# Water_Level_Indicator.net
KiCad netlist of a schematic drawn in Altium Designer
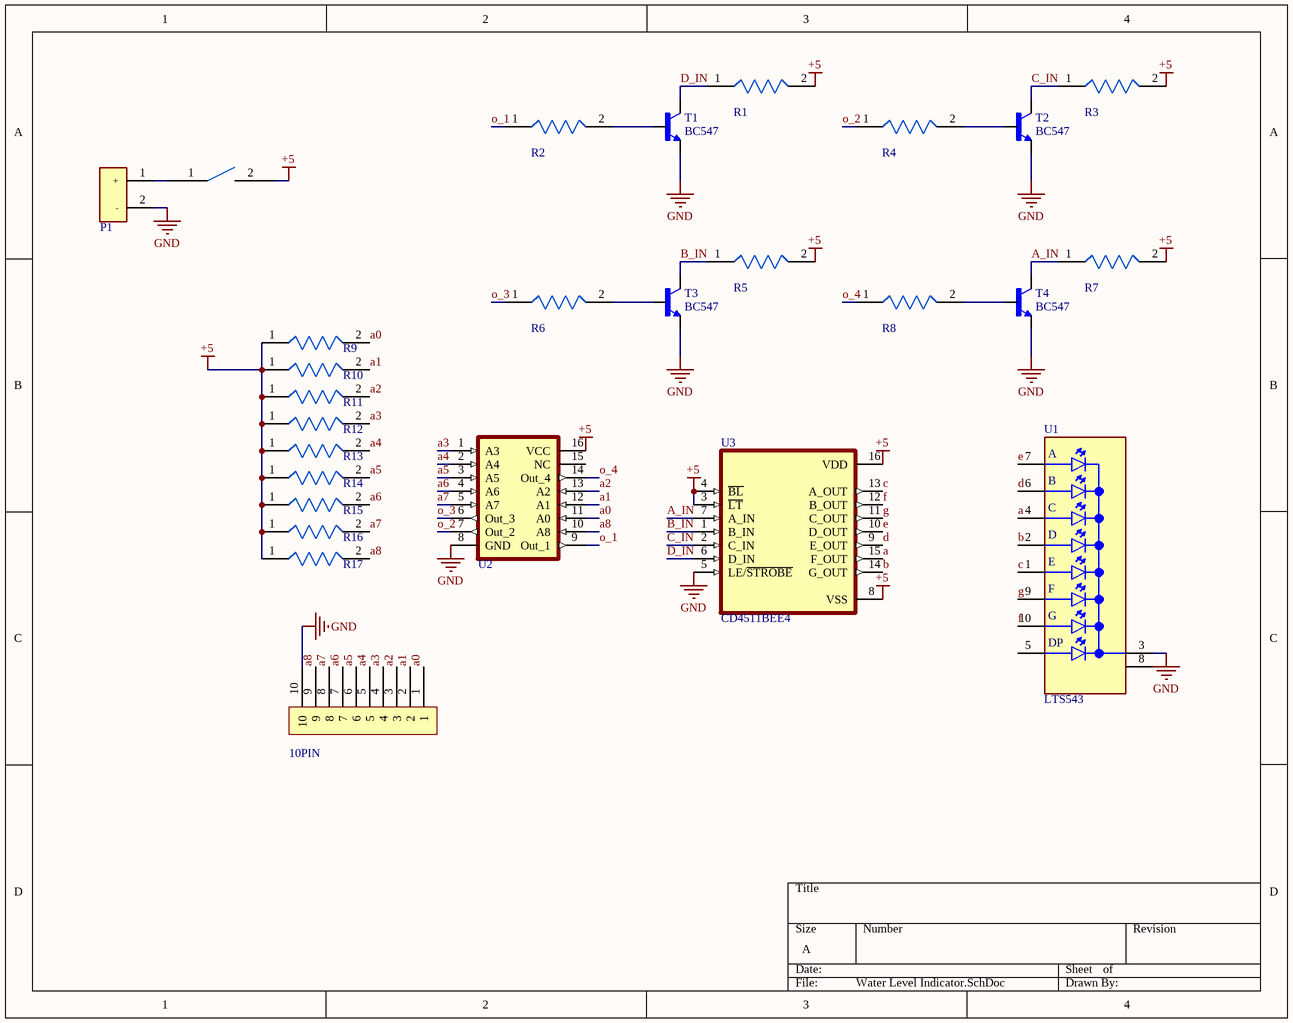
[diagram p0: Water Level Indicator.SchDoc]

(export (version "E")
  (design (tool "Eeschema 10.0.6"))
  (components
    (comp (ref "*") (value "10PIN") (footprint "10PIN") (libsource (lib "Problem_1_lib") (part "10PIN")))
    (comp (ref "P1")
      (value "HEADER, 2 PINS")
      (footprint "XT60 Male")
      (description "CONNECTOR")
      (libsource (lib "Problem_1_lib") (part "XT60 MALE"))
    )
    (comp (ref "R1")
      (value "Resistor (33k)")
      (footprint "Resistor (33k)")
      (libsource (lib "Problem_1_lib") (part "Resistor (33k)"))
    )
    (comp (ref "R2")
      (value "Resistor (12k)")
      (footprint "Resistor (12k)")
      (libsource (lib "Problem_1_lib") (part "Resistor (12k)"))
    )
    (comp (ref "R3")
      (value "Resistor (33k)")
      (footprint "Resistor (33k)")
      (libsource (lib "Problem_1_lib") (part "Resistor (33k)"))
    )
    (comp (ref "R4")
      (value "Resistor (12k)")
      (footprint "Resistor (12k)")
      (libsource (lib "Problem_1_lib") (part "Resistor (12k)"))
    )
    (comp (ref "R5")
      (value "Resistor (33k)")
      (footprint "Resistor (33k)")
      (libsource (lib "Problem_1_lib") (part "Resistor (33k)"))
    )
    (comp (ref "R6")
      (value "Resistor (12k)")
      (footprint "Resistor (12k)")
      (libsource (lib "Problem_1_lib") (part "Resistor (12k)"))
    )
    (comp (ref "R7")
      (value "Resistor (33k)")
      (footprint "Resistor (33k)")
      (libsource (lib "Problem_1_lib") (part "Resistor (33k)"))
    )
    (comp (ref "R8")
      (value "Resistor (12k)")
      (footprint "Resistor (12k)")
      (libsource (lib "Problem_1_lib") (part "Resistor (12k)"))
    )
    (comp (ref "R9")
      (value "Resistor (560k)")
      (footprint "Resistor (560k)")
      (libsource (lib "Problem_1_lib") (part "Resistor (560k)"))
    )
    (comp (ref "R10")
      (value "Resistor (560k)")
      (footprint "Resistor (560k)")
      (libsource (lib "Problem_1_lib") (part "Resistor (560k)"))
    )
    (comp (ref "R11")
      (value "Resistor (560k)")
      (footprint "Resistor (560k)")
      (libsource (lib "Problem_1_lib") (part "Resistor (560k)"))
    )
    (comp (ref "R12")
      (value "Resistor (560k)")
      (footprint "Resistor (560k)")
      (libsource (lib "Problem_1_lib") (part "Resistor (560k)"))
    )
    (comp (ref "R13")
      (value "Resistor (560k)")
      (footprint "Resistor (560k)")
      (libsource (lib "Problem_1_lib") (part "Resistor (560k)"))
    )
    (comp (ref "R14")
      (value "Resistor (560k)")
      (footprint "Resistor (560k)")
      (libsource (lib "Problem_1_lib") (part "Resistor (560k)"))
    )
    (comp (ref "R15")
      (value "Resistor (560k)")
      (footprint "Resistor (560k)")
      (libsource (lib "Problem_1_lib") (part "Resistor (560k)"))
    )
    (comp (ref "R16")
      (value "Resistor (560k)")
      (footprint "Resistor (560k)")
      (libsource (lib "Problem_1_lib") (part "Resistor (560k)"))
    )
    (comp (ref "R17")
      (value "Resistor (560k)")
      (footprint "Resistor (560k)")
      (libsource (lib "Problem_1_lib") (part "Resistor (560k)"))
    )
    (comp (ref "Switch")
      (value "Switch")
      (footprint "Switch")
      (description "Rocker Switch")
      (libsource (lib "Problem_1_lib") (part "Switch"))
    )
    (comp (ref "T1")
      (value "BC547")
      (footprint "BC547")
      (description "Trans GP BJT NPN 45V 0.1A 500mW 3-Pin TO-92 T/R")
      (fields (field (name "MF") "ON Semiconductor"))
      (libsource (lib "Problem_1_lib") (part "BC547"))
    )
    (comp (ref "T2")
      (value "BC547")
      (footprint "BC547")
      (description "Trans GP BJT NPN 45V 0.1A 500mW 3-Pin TO-92 T/R")
      (fields (field (name "MF") "ON Semiconductor"))
      (libsource (lib "Problem_1_lib") (part "BC547"))
    )
    (comp (ref "T3")
      (value "BC547")
      (footprint "BC547")
      (description "Trans GP BJT NPN 45V 0.1A 500mW 3-Pin TO-92 T/R")
      (fields (field (name "MF") "ON Semiconductor"))
      (libsource (lib "Problem_1_lib") (part "BC547"))
    )
    (comp (ref "T4")
      (value "BC547")
      (footprint "BC547")
      (description "Trans GP BJT NPN 45V 0.1A 500mW 3-Pin TO-92 T/R")
      (fields (field (name "MF") "ON Semiconductor"))
      (libsource (lib "Problem_1_lib") (part "BC547"))
    )
    (comp (ref "U1")
      (value "LTS543")
      (footprint "LTS543")
      (fields (field (name "MF") "Lumex Optoelectronics") (field (name "MP") "LDSC512RI"))
      (libsource (lib "Problem_1_lib") (part "LTS543"))
    )
    (comp (ref "U2")
      (value "74HC147")
      (footprint "74HC147")
      (fields (field (name "MP") "CD4511BEE4") (field (name "MF") "Texas Instruments"))
      (libsource (lib "Problem_1_lib") (part "74HC147"))
    )
    (comp (ref "U3")
      (value "CD4511BEE4")
      (footprint "CD4511BE")
      (description "CMOS BCD-to-7-Segment LED Latch Decoder Drivers 16-PDIP -55 to 125")
      (fields (field (name "MF") "Texas Instruments"))
      (libsource (lib "Problem_1_lib") (part "CD4511BEE4"))
    )
  )
  (nets
    (net (code "1") (name "+5") (class "Default")
      (node (ref "R1") (pin "2") (pintype "passive"))
      (node (ref "R10") (pin "1") (pintype "passive"))
      (node (ref "R11") (pin "1") (pintype "passive"))
      (node (ref "R12") (pin "1") (pintype "passive"))
      (node (ref "R13") (pin "1") (pintype "passive"))
      (node (ref "R14") (pin "1") (pintype "passive"))
      (node (ref "R15") (pin "1") (pintype "passive"))
      (node (ref "R16") (pin "1") (pintype "passive"))
      (node (ref "R17") (pin "1") (pintype "passive"))
      (node (ref "R3") (pin "2") (pintype "passive"))
      (node (ref "R5") (pin "2") (pintype "passive"))
      (node (ref "R7") (pin "2") (pintype "passive"))
      (node (ref "R9") (pin "1") (pintype "passive"))
      (node (ref "Switch") (pin "2") (pinfunction "9_2") (pintype "passive"))
      (node (ref "U2") (pin "16") (pinfunction "VCC_16") (pintype "power_in"))
      (node (ref "U3") (pin "16") (pinfunction "VDD_16") (pintype "power_in"))
      (node (ref "U3") (pin "3") (pinfunction "~{LT}_3") (pintype "input"))
      (node (ref "U3") (pin "4") (pinfunction "~{BL}_4") (pintype "input"))
      (node (ref "U3") (pin "8") (pinfunction "VSS_8") (pintype "power_in"))
    )
    (net (code "2") (name "/A_IN") (class "Default")
      (node (ref "R7") (pin "1") (pintype "passive"))
      (node (ref "T4") (pin "C") (pinfunction "C_C") (pintype "passive"))
      (node (ref "U3") (pin "7") (pinfunction "A_IN_7") (pintype "input"))
    )
    (net (code "3") (name "/B_IN") (class "Default")
      (node (ref "R5") (pin "1") (pintype "passive"))
      (node (ref "T3") (pin "C") (pinfunction "C_C") (pintype "passive"))
      (node (ref "U3") (pin "1") (pinfunction "B_IN_1") (pintype "input"))
    )
    (net (code "4") (name "/C_IN") (class "Default")
      (node (ref "R3") (pin "1") (pintype "passive"))
      (node (ref "T2") (pin "C") (pinfunction "C_C") (pintype "passive"))
      (node (ref "U3") (pin "2") (pinfunction "C_IN_2") (pintype "input"))
    )
    (net (code "5") (name "/D_IN") (class "Default")
      (node (ref "R1") (pin "1") (pintype "passive"))
      (node (ref "T1") (pin "C") (pinfunction "C_C") (pintype "passive"))
      (node (ref "U3") (pin "6") (pinfunction "D_IN_6") (pintype "input"))
    )
    (net (code "6") (name "/a") (class "Default")
      (node (ref "U1") (pin "4") (pinfunction "C_4") (pintype "passive"))
      (node (ref "U3") (pin "15") (pinfunction "F_OUT_15") (pintype "output"))
    )
    (net (code "7") (name "/a0") (class "Default")
      (node (ref "*") (pin "1") (pinfunction "1_1") (pintype "passive"))
      (node (ref "R9") (pin "2") (pintype "passive"))
      (node (ref "U2") (pin "11") (pinfunction "A0_11") (pintype "input"))
    )
    (net (code "8") (name "/a1") (class "Default")
      (node (ref "*") (pin "2") (pinfunction "2_2") (pintype "passive"))
      (node (ref "R10") (pin "2") (pintype "passive"))
      (node (ref "U2") (pin "12") (pinfunction "A1_12") (pintype "input"))
    )
    (net (code "9") (name "/a2") (class "Default")
      (node (ref "*") (pin "3") (pinfunction "3_3") (pintype "passive"))
      (node (ref "R11") (pin "2") (pintype "passive"))
      (node (ref "U2") (pin "13") (pinfunction "A2_13") (pintype "input"))
    )
    (net (code "10") (name "/a3") (class "Default")
      (node (ref "*") (pin "4") (pinfunction "4_4") (pintype "passive"))
      (node (ref "R12") (pin "2") (pintype "passive"))
      (node (ref "U2") (pin "1") (pinfunction "A3_1") (pintype "input"))
    )
    (net (code "11") (name "/a4") (class "Default")
      (node (ref "*") (pin "5") (pinfunction "5_5") (pintype "passive"))
      (node (ref "R13") (pin "2") (pintype "passive"))
      (node (ref "U2") (pin "2") (pinfunction "A4_2") (pintype "input"))
    )
    (net (code "12") (name "/a5") (class "Default")
      (node (ref "*") (pin "6") (pinfunction "6_6") (pintype "passive"))
      (node (ref "R14") (pin "2") (pintype "passive"))
      (node (ref "U2") (pin "3") (pinfunction "A5_3") (pintype "input"))
    )
    (net (code "13") (name "/a6") (class "Default")
      (node (ref "*") (pin "7") (pinfunction "7_7") (pintype "passive"))
      (node (ref "R15") (pin "2") (pintype "passive"))
      (node (ref "U2") (pin "4") (pinfunction "A6_4") (pintype "input"))
    )
    (net (code "14") (name "/a7") (class "Default")
      (node (ref "*") (pin "8") (pinfunction "8_8") (pintype "passive"))
      (node (ref "R16") (pin "2") (pintype "passive"))
      (node (ref "U2") (pin "5") (pinfunction "A7_5") (pintype "input"))
    )
    (net (code "15") (name "/a8") (class "Default")
      (node (ref "*") (pin "9") (pinfunction "9_9") (pintype "passive"))
      (node (ref "R17") (pin "2") (pintype "passive"))
      (node (ref "U2") (pin "10") (pinfunction "A8_10") (pintype "input"))
    )
    (net (code "16") (name "/b") (class "Default")
      (node (ref "U1") (pin "2") (pinfunction "D_2") (pintype "passive"))
      (node (ref "U3") (pin "14") (pinfunction "G_OUT_14") (pintype "output"))
    )
    (net (code "17") (name "/c") (class "Default")
      (node (ref "U1") (pin "1") (pinfunction "E_1") (pintype "passive"))
      (node (ref "U3") (pin "13") (pinfunction "A_OUT_13") (pintype "output"))
    )
    (net (code "18") (name "/d") (class "Default")
      (node (ref "U1") (pin "6") (pinfunction "B_6") (pintype "passive"))
      (node (ref "U3") (pin "9") (pinfunction "E_OUT_9") (pintype "output"))
    )
    (net (code "19") (name "/e") (class "Default")
      (node (ref "U1") (pin "7") (pinfunction "A_7") (pintype "passive"))
      (node (ref "U3") (pin "10") (pinfunction "D_OUT_10") (pintype "output"))
    )
    (net (code "20") (name "/f") (class "Default")
      (node (ref "U1") (pin "10") (pinfunction "G_10") (pintype "passive"))
      (node (ref "U3") (pin "12") (pinfunction "B_OUT_12") (pintype "output"))
    )
    (net (code "21") (name "/g") (class "Default")
      (node (ref "U1") (pin "9") (pinfunction "F_9") (pintype "passive"))
      (node (ref "U3") (pin "11") (pinfunction "C_OUT_11") (pintype "output"))
    )
    (net (code "22") (name "/o_1") (class "Default")
      (node (ref "R2") (pin "1") (pintype "passive"))
      (node (ref "U2") (pin "9") (pinfunction "Out_1_9") (pintype "output"))
    )
    (net (code "23") (name "/o_2") (class "Default")
      (node (ref "R4") (pin "1") (pintype "passive"))
      (node (ref "U2") (pin "7") (pinfunction "Out_2_7") (pintype "output"))
    )
    (net (code "24") (name "/o_3") (class "Default")
      (node (ref "R6") (pin "1") (pintype "passive"))
      (node (ref "U2") (pin "6") (pinfunction "Out_3_6") (pintype "output"))
    )
    (net (code "25") (name "/o_4") (class "Default")
      (node (ref "R8") (pin "1") (pintype "passive"))
      (node (ref "U2") (pin "14") (pinfunction "Out_4_14") (pintype "output"))
    )
    (net (code "26") (name "GND") (class "Default")
      (node (ref "*") (pin "10") (pinfunction "10_10") (pintype "passive"))
      (node (ref "P1") (pin "2") (pinfunction "-_2") (pintype "passive"))
      (node (ref "T1") (pin "E") (pinfunction "E_E") (pintype "passive"))
      (node (ref "T2") (pin "E") (pinfunction "E_E") (pintype "passive"))
      (node (ref "T3") (pin "E") (pinfunction "E_E") (pintype "passive"))
      (node (ref "T4") (pin "E") (pinfunction "E_E") (pintype "passive"))
      (node (ref "U1") (pin "3") (pinfunction "CC_3") (pintype "passive"))
      (node (ref "U2") (pin "8") (pinfunction "GND_8") (pintype "passive"))
      (node (ref "U3") (pin "5") (pinfunction "LE/~{STROBE}_5") (pintype "input"))
    )
    (net (code "27") (name "Net-(P1-+)") (class "Default")
      (node (ref "P1") (pin "1") (pinfunction "+_1") (pintype "passive"))
      (node (ref "Switch") (pin "1") (pinfunction "8_1") (pintype "passive"))
    )
    (net (code "28") (name "Net-(R2-Pad2)") (class "Default")
      (node (ref "R2") (pin "2") (pintype "passive"))
      (node (ref "T1") (pin "B") (pinfunction "B_B") (pintype "passive"))
    )
    (net (code "29") (name "Net-(R4-Pad2)") (class "Default")
      (node (ref "R4") (pin "2") (pintype "passive"))
      (node (ref "T2") (pin "B") (pinfunction "B_B") (pintype "passive"))
    )
    (net (code "30") (name "Net-(R6-Pad2)") (class "Default")
      (node (ref "R6") (pin "2") (pintype "passive"))
      (node (ref "T3") (pin "B") (pinfunction "B_B") (pintype "passive"))
    )
    (net (code "31") (name "Net-(R8-Pad2)") (class "Default")
      (node (ref "R8") (pin "2") (pintype "passive"))
      (node (ref "T4") (pin "B") (pinfunction "B_B") (pintype "passive"))
    )
    (net (code "32") (name "unconnected-(U1-CC-Pad8)") (class "Default")
      (node (ref "U1") (pin "8") (pinfunction "CC_8") (pintype "passive"))
    )
    (net (code "33") (name "unconnected-(U1-DP-Pad5)") (class "Default")
      (node (ref "U1") (pin "5") (pinfunction "DP_5") (pintype "passive"))
    )
    (net (code "34") (name "unconnected-(U2-NC-Pad15)") (class "Default")
      (node (ref "U2") (pin "15") (pinfunction "NC_15") (pintype "passive"))
    )
  )
)
